# GNSS.net
KiCad netlist of a schematic drawn in Altium Designer
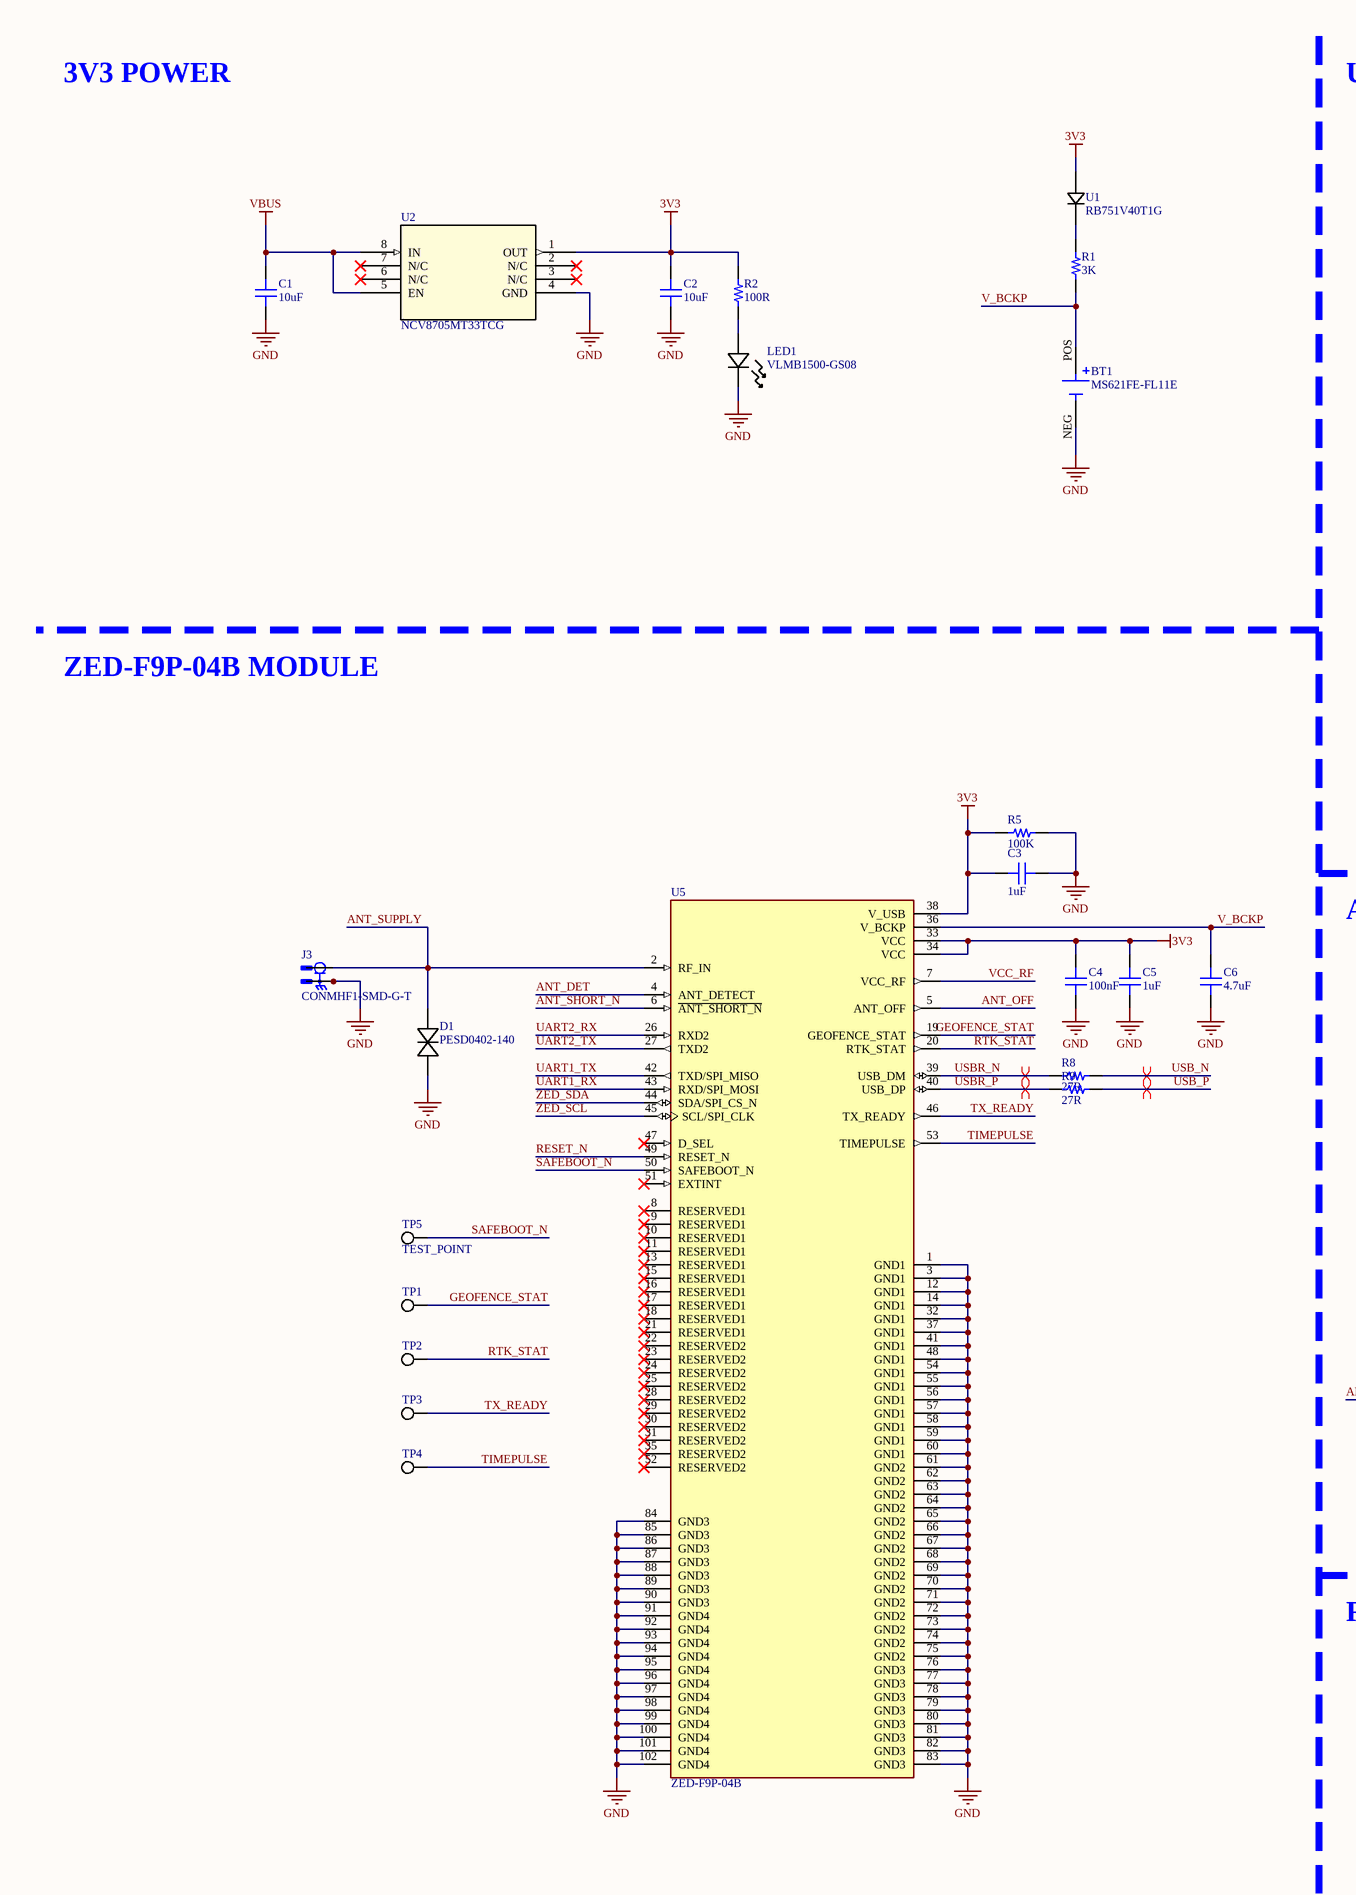
[diagram p0: GNSS.SchDoc, left]
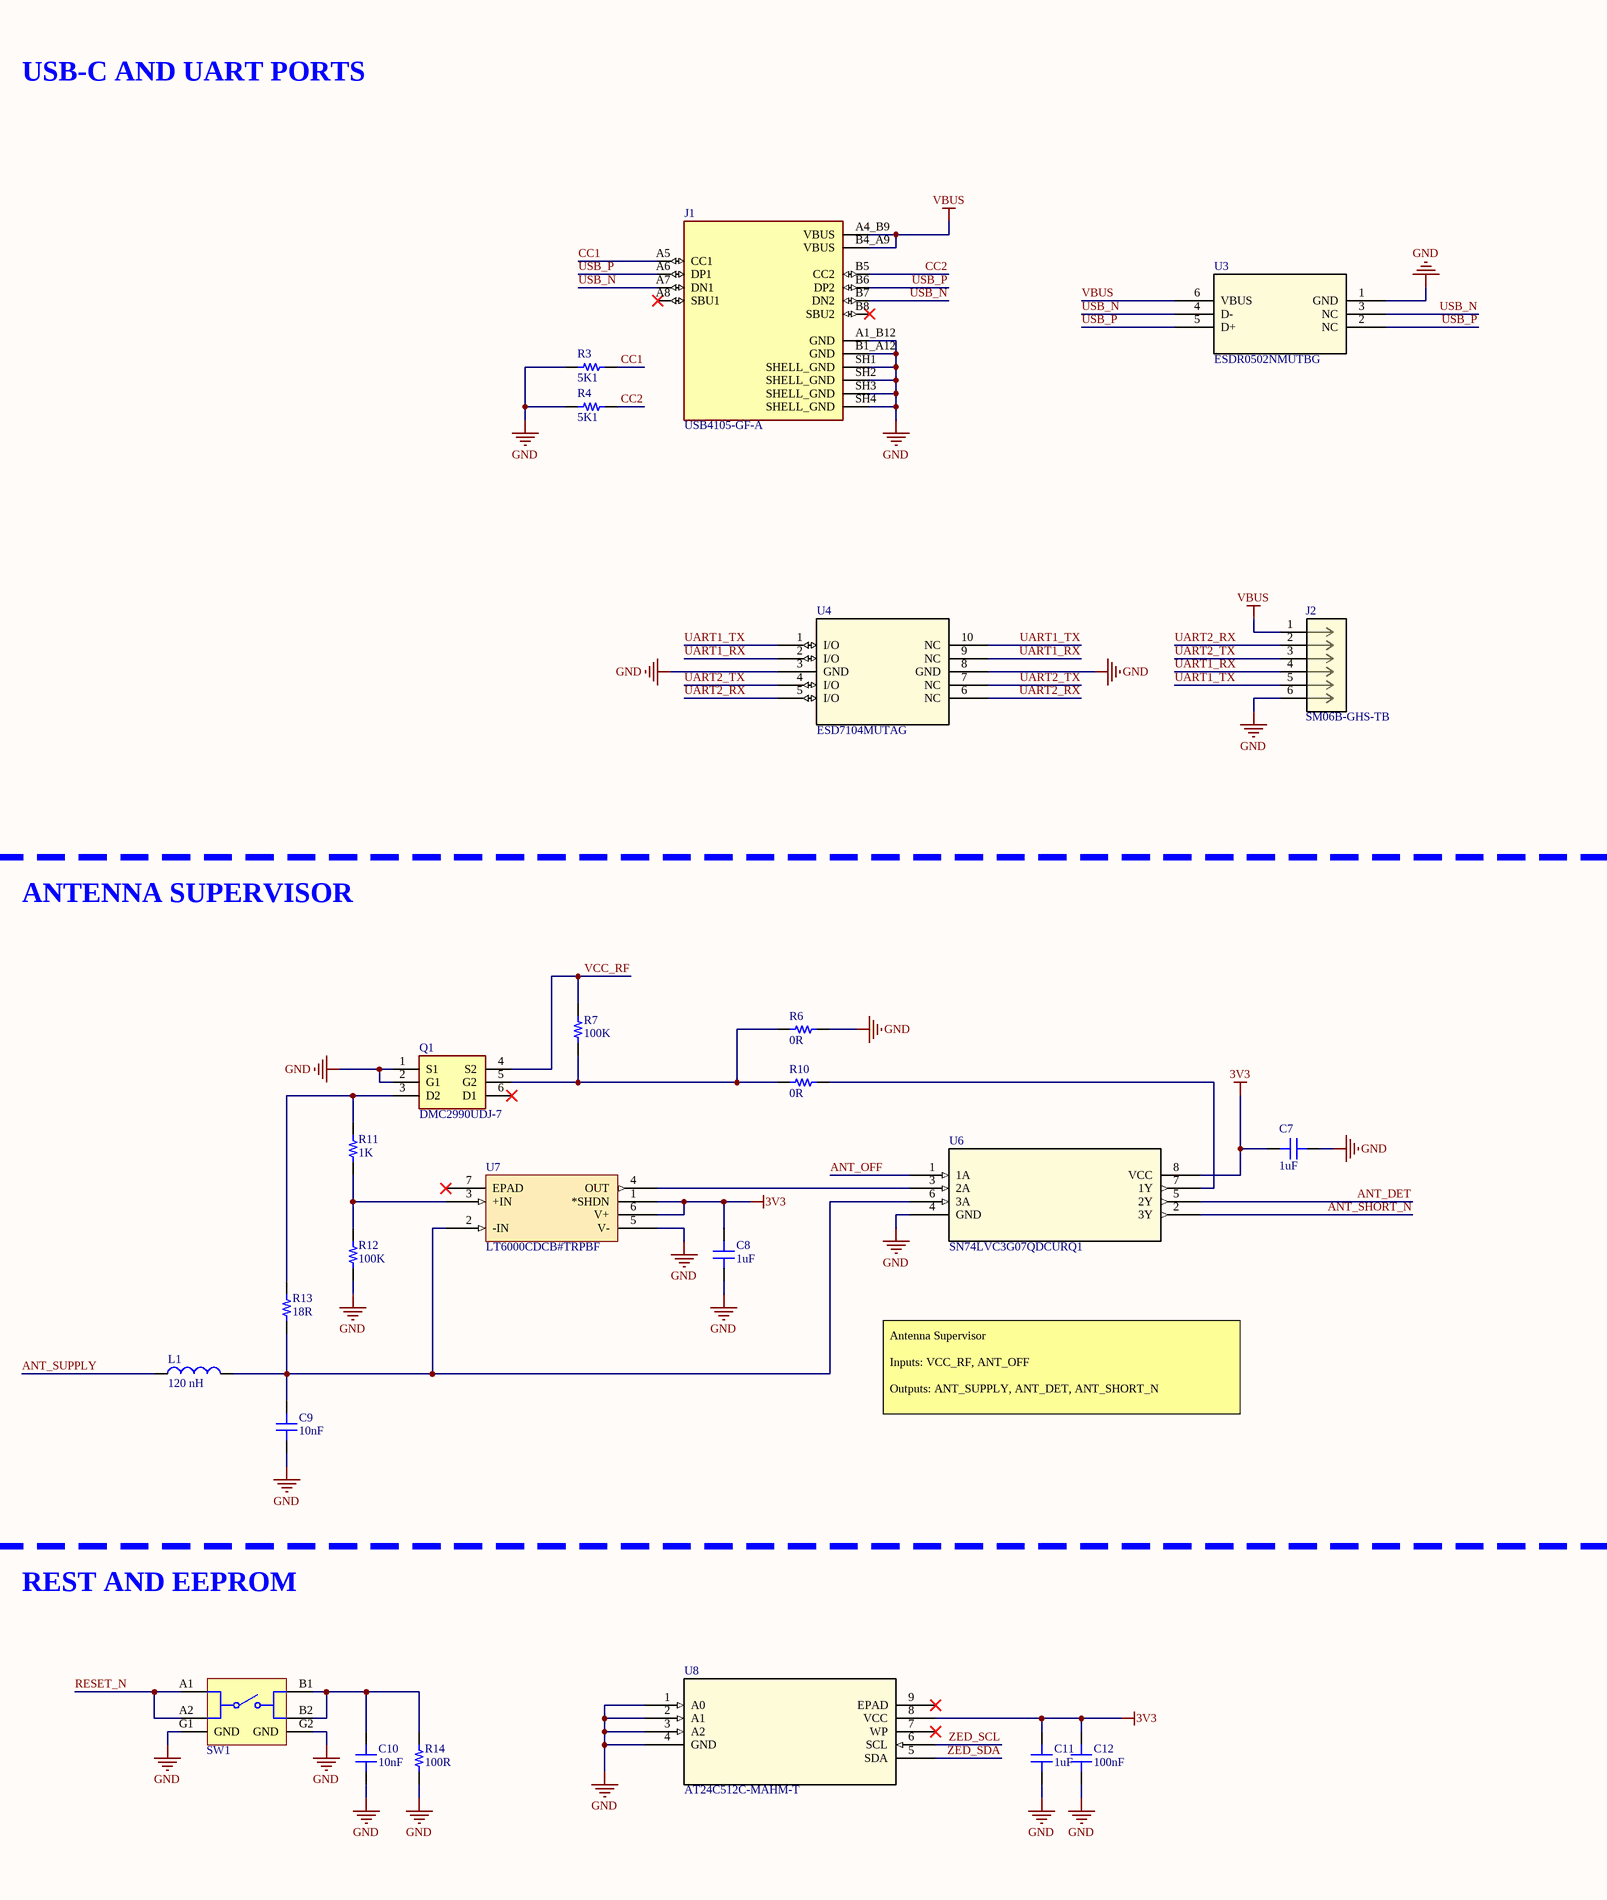
[diagram p1: GNSS.SchDoc, right]

(export (version "E")
  (design (tool "Eeschema 10.0.6"))
  (components
    (comp (ref "BT1")
      (value "MS621FE-FL11E")
      (footprint "BAT_MS621FE-FL11E")
      (description "Coin, 6.8mm 3 V Lithium Battery Rechargeable (Secondary) 5.5mAh")
      (fields (field (name "MF") "Seiko Instruments"))
      (libsource (lib "GPS-Module-Schlib") (part "MS621FE-FL11E"))
    )
    (comp (ref "C1")
      (value "10uF")
      (footprint "CAP 0402_1005")
      (description "Ceramic Capacitor, Ceramic, 10V, 20% +Tol, 20% -Tol, X5R, 15% TC, 10uF, Surface Mount, 0402")
      (fields (field (name "MANUFACTURER") "Murata") (field (name "MPN") "GRM155R61A106ME11D"))
      (libsource (lib "GPS-Module-Schlib") (part "GRM155R61A106ME11D"))
    )
    (comp (ref "C2")
      (value "10uF")
      (footprint "CAP 0402_1005")
      (description "Ceramic Capacitor, Ceramic, 10V, 20% +Tol, 20% -Tol, X5R, 15% TC, 10uF, Surface Mount, 0402")
      (fields (field (name "MANUFACTURER") "Murata") (field (name "MPN") "GRM155R61A106ME11D"))
      (libsource (lib "GPS-Module-Schlib") (part "GRM155R61A106ME11D"))
    )
    (comp (ref "C3")
      (value "1uF")
      (footprint "CAP 0402_1005")
      (description "Ceramic Capacitor, Ceramic, 16V, 10% +Tol, 10% -Tol, X6S, 22% TC, 1uF, Surface Mount, 0402")
      (fields (field (name "MANUFACTURER") "Murata") (field (name "MPN") "GRM155C81C105KE11D"))
      (libsource (lib "GPS-Module-Schlib") (part "GRM155C81C105KE11D"))
    )
    (comp (ref "C4")
      (value "100nF")
      (footprint "CAP 0402_1005")
      (description "Capacitor, Multilayer, Ceramic, 10V, 10%, X7R, 15% Tc, 0.1Uf, Surface Mount, 0402")
      (fields (field (name "MANUFACTURER") "KEMET") (field (name "MPN") "C0402C104K8RACTU"))
      (libsource (lib "GPS-Module-Schlib") (part "C0402C104K8RACTU"))
    )
    (comp (ref "C5")
      (value "1uF")
      (footprint "CAP 0402_1005")
      (description "Ceramic Capacitor, Ceramic, 16V, 10% +Tol, 10% -Tol, X6S, 22% TC, 1uF, Surface Mount, 0402")
      (fields (field (name "MANUFACTURER") "Murata") (field (name "MPN") "GRM155C81C105KE11D"))
      (libsource (lib "GPS-Module-Schlib") (part "GRM155C81C105KE11D"))
    )
    (comp (ref "C6")
      (value "4.7uF")
      (footprint "CAP 0603_1608")
      (description "Multilayer Ceramic Capacitor, CC Series, 4.7 - F, - 10%, X5R, 6.3 V, 0603 [1608 Metric]")
      (fields (field (name "MANUFACTURER") "Yageo Group") (field (name "MPN") "CC0603KRX5R5BB475"))
      (libsource (lib "GPS-Module-Schlib") (part "CC0603KRX5R5BB475"))
    )
    (comp (ref "C7")
      (value "1uF")
      (footprint "CAP 0402_1005")
      (description "Ceramic Capacitor, Ceramic, 16V, 10% +Tol, 10% -Tol, X6S, 22% TC, 1uF, Surface Mount, 0402")
      (fields (field (name "MANUFACTURER") "Murata") (field (name "MPN") "GRM155C81C105KE11D"))
      (libsource (lib "GPS-Module-Schlib") (part "GRM155C81C105KE11D"))
    )
    (comp (ref "C8")
      (value "1uF")
      (footprint "CAP 0402_1005")
      (description "Ceramic Capacitor, Ceramic, 16V, 10% +Tol, 10% -Tol, X6S, 22% TC, 1uF, Surface Mount, 0402")
      (fields (field (name "MANUFACTURER") "Murata") (field (name "MPN") "GRM155C81C105KE11D"))
      (libsource (lib "GPS-Module-Schlib") (part "GRM155C81C105KE11D"))
    )
    (comp (ref "C9")
      (value "10nF")
      (footprint "CAP 0402_1005")
      (description "0402 10000 pF 16 V ±10% Tolerance X7R Multilayer Ceramic Chip Capacitor")
      (fields (field (name "MANUFACTURER") "Murata") (field (name "MPN") "GRM155R71C103KA01D"))
      (libsource (lib "GPS-Module-Schlib") (part "GRM155R71C103KA01D"))
    )
    (comp (ref "C10")
      (value "10nF")
      (footprint "CAP 0402_1005")
      (description "Multilayer Ceramic Capacitors MLCC - SMD/SMT 25V 0.01uF X7R 0402 10%")
      (fields (field (name "MANUFACTURER") "KEMET") (field (name "MPN") "C0402C103K3REC7411"))
      (libsource (lib "GPS-Module-Schlib") (part "C0402C103K3REC7411"))
    )
    (comp (ref "C11")
      (value "1uF")
      (footprint "CAP 0402_1005")
      (description "Ceramic Capacitor, Ceramic, 16V, 10% +Tol, 10% -Tol, X6S, 22% TC, 1uF, Surface Mount, 0402")
      (fields (field (name "MANUFACTURER") "Murata") (field (name "MPN") "GRM155C81C105KE11D"))
      (libsource (lib "GPS-Module-Schlib") (part "GRM155C81C105KE11D"))
    )
    (comp (ref "C12")
      (value "100nF")
      (footprint "CAP 0402_1005")
      (description "Capacitor, Multilayer, Ceramic, 10V, 10%, X7R, 15% Tc, 0.1Uf, Surface Mount, 0402")
      (fields (field (name "MANUFACTURER") "KEMET") (field (name "MPN") "C0402C104K8RACTU"))
      (libsource (lib "GPS-Module-Schlib") (part "C0402C104K8RACTU"))
    )
    (comp (ref "D1")
      (value "PESD0402-140")
      (footprint "PESD0402-140_LTF")
      (description "TVS DIODE 14VWM 40VC 0402")
      (fields (field (name "COPYRIGHT") "Copyright (C) 2025 Ultra Librarian. All rights reserved."))
      (libsource (lib "GPS-Module-Schlib") (part "PESD0402-140"))
    )
    (comp (ref "J1")
      (value "USB4105-GF-A")
      (footprint "GCT_USB4105-GF-A")
      (description "CONN RCP USB2.0 TYP C 24P SMD RA")
      (fields (field (name "MF") "{'manufacturer': u'GCT'}"))
      (libsource (lib "GPS-Module-Schlib") (part "USB4105-GF-A"))
    )
    (comp (ref "J2")
      (value "SM06B-GHS-TB")
      (footprint "CONN_SM06B-GHS-TB_JST")
      (description "CONN HEADER SMD R/A 6POS 1.25MM")
      (fields (field (name "COPYRIGHT") "Copyright (C) 2025 Ultra Librarian. All rights reserved."))
      (libsource (lib "GPS-Module-Schlib") (part "SM06B-GHS-TB"))
    )
    (comp (ref "J3")
      (value "CONMHF1-SMD-G-T")
      (footprint "LINX_CONMHF1-SMD-G-T")
      (description "U.FL/MHF1 Jack 50 Ohm PCB Surface Mount")
      (fields (field (name "MF") "TE Connectivity"))
      (libsource (lib "GPS-Module-Schlib") (part "CONMHF1-SMD-G-T"))
    )
    (comp (ref "L1")
      (value "120 nH")
      (footprint "INDC1005X60N")
      (description "Inductor with Inductance: 120nH Tol. +/-5%, Package: 0402 _1005_")
      (fields (field (name "DIGI-KEY_PART_NUMBER") "490-4091-1-ND") (field (name "MPN") "LQW15ANR12J00D"))
      (libsource (lib "GPS-Module-Schlib") (part "LQW15ANR12J00D"))
    )
    (comp (ref "LED1")
      (value "VLMB1500-GS08")
      (footprint "LED_500-GS08_VIS")
      (description "CHIPLED(0402) BLUE ULTRABRIGHT -e4")
      (fields (field (name "COPYRIGHT") "Copyright (C) 2025 Ultra Librarian. All rights reserved."))
      (libsource (lib "GPS-Module-Schlib") (part "VLMB1500-GS08"))
    )
    (comp (ref "Q1")
      (value "DMC2990UDJ-7")
      (footprint "SOTFL35P100X50-6N")
      (description "Complem. Pair Enhancement MOSFET SOT-963")
      (fields (field (name "MOUSER PART NUMBER") "621-DMC2990UDJ-7"))
      (libsource (lib "GPS-Module-Schlib") (part "DMC2990UDJ-7"))
    )
    (comp (ref "R1")
      (value "3K")
      (footprint "RES 0402_1005")
      (description "Res Thick Film 0402 3K Ohm 1% 0.1W ±100ppm/°C Molded SMD Punched Carrier T/R")
      (fields (field (name "MANUFACTURER") "Panasonic") (field (name "MPN") "ERJ-2RKF3001X"))
      (libsource (lib "GPS-Module-Schlib") (part "ERJ-2RKF3001X"))
    )
    (comp (ref "R2")
      (value "100R")
      (footprint "RES 0402_1005")
      (description "Res Thick Film 0402 100 Ohm 1% 0.2W ±100ppm/°C Molded SMD SMD Paper T/R")
      (fields (field (name "MANUFACTURER") "Vishay") (field (name "MPN") "CRCW0402100RFKEDHP"))
      (libsource (lib "GPS-Module-Schlib") (part "CRCW0402100RFKEDHP"))
    )
    (comp (ref "R3")
      (value "5K1")
      (footprint "RES 0402_1005")
      (description "Res Thick Film 0402 5.1K Ohm 1% 0.063W(1/16W) ±100ppm/C Pad SMD T/R")
      (fields (field (name "MANUFACTURER") "Yageo Group") (field (name "MPN") "RC0402FR-135K1L"))
      (libsource (lib "GPS-Module-Schlib") (part "RC0402FR-135K1L"))
    )
    (comp (ref "R4")
      (value "5K1")
      (footprint "RES 0402_1005")
      (description "Res Thick Film 0402 5.1K Ohm 1% 0.063W(1/16W) ±100ppm/C Pad SMD T/R")
      (fields (field (name "MANUFACTURER") "Yageo Group") (field (name "MPN") "RC0402FR-135K1L"))
      (libsource (lib "GPS-Module-Schlib") (part "RC0402FR-135K1L"))
    )
    (comp (ref "R5")
      (value "100K")
      (footprint "RES 0402_1005")
      (description "Res Thick Film 0402 100K Ohm 1% 0.063W(1/16W) ±100ppm/C Pad SMD T/R")
      (fields (field (name "MANUFACTURER") "Vishay") (field (name "MPN") "CRCW0402100KFKEDC"))
      (libsource (lib "GPS-Module-Schlib") (part "CRCW0402100KFKEDC"))
    )
    (comp (ref "R6")
      (value "0R")
      (footprint "RES 0402_1005")
      (description "GENERAL PURPOSE CHIP RESISTOR Metal Glaze/thick Film, 0.0625W, 0ohm, Surface Mount, 0402")
      (fields (field (name "MANUFACTURER") "Yageo Group") (field (name "MPN") "RC0402JR-070RL"))
      (libsource (lib "GPS-Module-Schlib") (part "RC0402JR-070RL"))
    )
    (comp (ref "R7")
      (value "100K")
      (footprint "RES 0402_1005")
      (description "Res Thick Film 0402 100K Ohm 1% 0.063W(1/16W) ±100ppm/C Pad SMD T/R")
      (fields (field (name "MANUFACTURER") "Vishay") (field (name "MPN") "CRCW0402100KFKEDC"))
      (libsource (lib "GPS-Module-Schlib") (part "CRCW0402100KFKEDC"))
    )
    (comp (ref "R8")
      (value "27R")
      (footprint "RES 0402_1005")
      (description "Res General Purpose Thick Film 0402 27 Ohm 5% 1/16W ±100ppm/°C Molded SMD Paper T/R")
      (fields (field (name "MANUFACTURER") "Yageo Group") (field (name "MPN") "RC0402JR-0727RL"))
      (libsource (lib "GPS-Module-Schlib") (part "RC0402JR-0727RL"))
    )
    (comp (ref "R9")
      (value "27R")
      (footprint "RES 0402_1005")
      (description "Res General Purpose Thick Film 0402 27 Ohm 5% 1/16W ±100ppm/°C Molded SMD Paper T/R")
      (fields (field (name "MANUFACTURER") "Yageo Group") (field (name "MPN") "RC0402JR-0727RL"))
      (libsource (lib "GPS-Module-Schlib") (part "RC0402JR-0727RL"))
    )
    (comp (ref "R10")
      (value "0R")
      (footprint "RES 0402_1005")
      (description "GENERAL PURPOSE CHIP RESISTOR Metal Glaze/thick Film, 0.0625W, 0ohm, Surface Mount, 0402")
      (fields (field (name "MANUFACTURER") "Yageo Group") (field (name "MPN") "RC0402JR-070RL"))
      (libsource (lib "GPS-Module-Schlib") (part "RC0402JR-070RL"))
    )
    (comp (ref "R11")
      (value "1K")
      (footprint "RES 0402_1005")
      (description "Res Thick Film 0402 1K Ohm 1% 0.063W(1/16W) ±100ppm/C Pad SMD T/R")
      (fields (field (name "MANUFACTURER") "Vishay") (field (name "MPN") "CRCW04021K00FKEDC"))
      (libsource (lib "GPS-Module-Schlib") (part "CRCW04021K00FKEDC"))
    )
    (comp (ref "R12")
      (value "100K")
      (footprint "RES 0402_1005")
      (description "Res Thick Film 0402 100K Ohm 1% 0.063W(1/16W) ±100ppm/C Pad SMD T/R")
      (fields (field (name "MANUFACTURER") "Vishay") (field (name "MPN") "CRCW0402100KFKEDC"))
      (libsource (lib "GPS-Module-Schlib") (part "CRCW0402100KFKEDC"))
    )
    (comp (ref "R13")
      (value "18R")
      (footprint "RES 0402_1005")
      (description "Res Thick Film 0402 18 Ohm 1% 0.063W(1/16W) ±100ppm/C Pad SMD T/R")
      (fields (field (name "MANUFACTURER") "Bourns") (field (name "MPN") "CR0402-FX-18R0GLF"))
      (libsource (lib "GPS-Module-Schlib") (part "CR0402-FX-18R0GLF"))
    )
    (comp (ref "R14")
      (value "100R")
      (footprint "RES 0402_1005")
      (description "Res Thick Film 0402 100 Ohm 1% 0.2W ±100ppm/°C Molded SMD SMD Paper T/R")
      (fields (field (name "MANUFACTURER") "Vishay") (field (name "MPN") "CRCW0402100RFKEDHP"))
      (libsource (lib "GPS-Module-Schlib") (part "CRCW0402100RFKEDHP"))
    )
    (comp (ref "SW1")
      (value "435151014845")
      (footprint "435151014845")
      (description "WS-TASV SMT Tact Switch with ground terminal, L3 x W2.6 x H1.4mm, 450g, SPST-NO, 12V, 50mA")
      (fields (field (name "MANUFACTURER") "Wurth Elektronik"))
      (libsource (lib "GPS-Module-Schlib") (part "435151014845"))
    )
    (comp (ref "TP1")
      (value "TEST_POINT")
      (footprint "TEST_POINT")
      (libsource (lib "GPS-Module-Schlib") (part "TEST_POINT"))
    )
    (comp (ref "TP2")
      (value "TEST_POINT")
      (footprint "TEST_POINT")
      (libsource (lib "GPS-Module-Schlib") (part "TEST_POINT"))
    )
    (comp (ref "TP3")
      (value "TEST_POINT")
      (footprint "TEST_POINT")
      (libsource (lib "GPS-Module-Schlib") (part "TEST_POINT"))
    )
    (comp (ref "TP4")
      (value "TEST_POINT")
      (footprint "TEST_POINT")
      (libsource (lib "GPS-Module-Schlib") (part "TEST_POINT"))
    )
    (comp (ref "TP5")
      (value "TEST_POINT")
      (footprint "TEST_POINT")
      (libsource (lib "GPS-Module-Schlib") (part "TEST_POINT"))
    )
    (comp (ref "U1")
      (value "RB751V40T1G")
      (footprint "SOD-323_1P8X1P35_ONS")
      (description "Diode 30 V 30mA Surface Mount SOD-323")
      (fields (field (name "COPYRIGHT") "Copyright (C) 2025 Ultra Librarian. All rights reserved."))
      (libsource (lib "GPS-Module-Schlib") (part "RB751V40T1G"))
    )
    (comp (ref "U2")
      (value "NCV8705MT33TCG")
      (footprint "WDFN6_2X2_ONS")
      (description "Linear Voltage Regulator IC Positive Fixed 1 Output 500mA 6-WDFN (2x2)")
      (fields (field (name "COPYRIGHT") "Copyright (C) 2025 Ultra Librarian. All rights reserved."))
      (libsource (lib "GPS-Module-Schlib") (part "NCV8705MT33TCG"))
    )
    (comp (ref "U3")
      (value "ESDR0502NMUTBG")
      (footprint "UDFN6_517AA_ONS")
      (description "TVS DIODE 5.5VWM 6UDFN")
      (fields (field (name "COPYRIGHT") "Copyright (C) 2025 Ultra Librarian. All rights reserved."))
      (libsource (lib "GPS-Module-Schlib") (part "ESDR0502NMUTBG"))
    )
    (comp (ref "U4")
      (value "ESD7104MUTAG")
      (footprint "UDFN10_ONS_ESD")
      (description "TVS DIODE 5VWM 10VC 10UDFN")
      (fields (field (name "COPYRIGHT") "Copyright (C) 2025 Ultra Librarian. All rights reserved."))
      (libsource (lib "GPS-Module-Schlib") (part "ESD7104MUTAG"))
    )
    (comp (ref "U5")
      (value "ZED-F9P-04B")
      (footprint "MODULE_ZED-F9P-04B")
      (fields (field (name "MF") "U-Blox"))
      (libsource (lib "GPS-Module-Schlib") (part "ZED-F9P-04B"))
    )
    (comp (ref "U6")
      (value "SN74LVC3G07QDCURQ1")
      (footprint "DCU8_TEX_SN74")
      (description "Automotive 3-ch, 1.65-V to 5.5-V buffers with open-drain outputs 8-VSSOP -40 to 125")
      (fields (field (name "COPYRIGHT") "Copyright (C) 2025 Ultra Librarian. All rights reserved."))
      (libsource (lib "GPS-Module-Schlib") (part "SN74LVC3G07QDCURQ1"))
    )
    (comp (ref "U7")
      (value "LT6000CDCB#TRPBF")
      (footprint "DFN-6_DCB")
      (description "Op Amp Single Low Power Amplifier R-R I/O 18V Automotive 6-Pin DFN EP T/R")
      (fields (field (name "MF") "Analog Devices"))
      (libsource (lib "GPS-Module-Schlib") (part "LT6000CDCB#TRPBF"))
    )
    (comp (ref "U8")
      (value "AT24C512C-MAHM-T")
      (footprint "8MA2_ATM_EEPROM")
      (description "IC EEPROM 512KBIT I2C 8UDFN")
      (fields (field (name "COPYRIGHT") "Copyright (C) 2025 Ultra Librarian. All rights reserved."))
      (libsource (lib "GPS-Module-Schlib") (part "AT24C512C-MAHM-T"))
    )
  )
  (nets
    (net (code "1") (name "/ANT_DET") (class "Default")
      (node (ref "U5") (pin "4") (pinfunction "ANT_DETECT_4") (pintype "input"))
      (node (ref "U6") (pin "5") (pinfunction "2Y_5") (pintype "output"))
    )
    (net (code "2") (name "/ANT_OFF") (class "Default")
      (node (ref "U5") (pin "5") (pinfunction "ANT_OFF_5") (pintype "output"))
      (node (ref "U6") (pin "1") (pinfunction "1A_1") (pintype "input"))
    )
    (net (code "3") (name "/ANT_SHORT_N") (class "Default")
      (node (ref "U5") (pin "6") (pinfunction "~{ANT_SHORT_N}_6") (pintype "input"))
      (node (ref "U6") (pin "2") (pinfunction "3Y_2") (pintype "output"))
    )
    (net (code "4") (name "/ANT_SUPPLY") (class "Default")
      (node (ref "D1") (pin "1") (pinfunction "1_1") (pintype "passive"))
      (node (ref "J3") (pin "1") (pinfunction "1_1") (pintype "passive"))
      (node (ref "L1") (pin "1") (pinfunction "1_1") (pintype "passive"))
      (node (ref "U5") (pin "2") (pinfunction "RF_IN_2") (pintype "input"))
    )
    (net (code "5") (name "/CC1") (class "Default")
      (node (ref "J1") (pin "A5") (pinfunction "CC1_A5") (pintype "bidirectional"))
      (node (ref "R3") (pin "1") (pinfunction "1_1") (pintype "passive"))
    )
    (net (code "6") (name "/CC2") (class "Default")
      (node (ref "J1") (pin "B5") (pinfunction "CC2_B5") (pintype "bidirectional"))
      (node (ref "R4") (pin "2") (pinfunction "2_2") (pintype "passive"))
    )
    (net (code "7") (name "/GEOFENCE_STAT") (class "Default")
      (node (ref "TP1") (pin "1") (pinfunction "1_1") (pintype "passive"))
      (node (ref "U5") (pin "19") (pinfunction "GEOFENCE_STAT_19") (pintype "output"))
    )
    (net (code "8") (name "/RESET_N") (class "Default")
      (node (ref "SW1") (pin "A1") (pinfunction "A1_A1") (pintype "passive"))
      (node (ref "SW1") (pin "A2") (pinfunction "A2_A2") (pintype "passive"))
      (node (ref "U5") (pin "49") (pinfunction "RESET_N_49") (pintype "input"))
    )
    (net (code "9") (name "/RTK_STAT") (class "Default")
      (node (ref "TP2") (pin "1") (pinfunction "1_1") (pintype "passive"))
      (node (ref "U5") (pin "20") (pinfunction "RTK_STAT_20") (pintype "output"))
    )
    (net (code "10") (name "/SAFEBOOT_N") (class "Default")
      (node (ref "TP5") (pin "1") (pinfunction "1_1") (pintype "passive"))
      (node (ref "U5") (pin "50") (pinfunction "SAFEBOOT_N_50") (pintype "input"))
    )
    (net (code "11") (name "/TIMEPULSE") (class "Default")
      (node (ref "TP4") (pin "1") (pinfunction "1_1") (pintype "passive"))
      (node (ref "U5") (pin "53") (pinfunction "TIMEPULSE_53") (pintype "output"))
    )
    (net (code "12") (name "/TX_READY") (class "Default")
      (node (ref "TP3") (pin "1") (pinfunction "1_1") (pintype "passive"))
      (node (ref "U5") (pin "46") (pinfunction "TX_READY_46") (pintype "output"))
    )
    (net (code "13") (name "/UART1_RX") (class "Default")
      (node (ref "J2") (pin "4") (pinfunction "4_4") (pintype "passive"))
      (node (ref "U4") (pin "2") (pinfunction "I/O_2") (pintype "bidirectional"))
      (node (ref "U4") (pin "9") (pinfunction "NC_9") (pintype "passive"))
      (node (ref "U5") (pin "43") (pinfunction "RXD/SPI_MOSI_43") (pintype "input"))
    )
    (net (code "14") (name "/UART1_TX") (class "Default")
      (node (ref "J2") (pin "5") (pinfunction "5_5") (pintype "passive"))
      (node (ref "U4") (pin "1") (pinfunction "I/O_1") (pintype "bidirectional"))
      (node (ref "U4") (pin "10") (pinfunction "NC_10") (pintype "passive"))
      (node (ref "U5") (pin "42") (pinfunction "TXD/SPI_MISO_42") (pintype "output"))
    )
    (net (code "15") (name "/UART2_RX") (class "Default")
      (node (ref "J2") (pin "2") (pinfunction "2_2") (pintype "passive"))
      (node (ref "U4") (pin "5") (pinfunction "I/O_5") (pintype "bidirectional"))
      (node (ref "U4") (pin "6") (pinfunction "NC_6") (pintype "passive"))
      (node (ref "U5") (pin "26") (pinfunction "RXD2_26") (pintype "input"))
    )
    (net (code "16") (name "/UART2_TX") (class "Default")
      (node (ref "J2") (pin "3") (pinfunction "3_3") (pintype "passive"))
      (node (ref "U4") (pin "4") (pinfunction "I/O_4") (pintype "bidirectional"))
      (node (ref "U4") (pin "7") (pinfunction "NC_7") (pintype "passive"))
      (node (ref "U5") (pin "27") (pinfunction "TXD2_27") (pintype "output"))
    )
    (net (code "17") (name "/USBR_N") (class "Default")
      (node (ref "R8") (pin "1") (pinfunction "1_1") (pintype "passive"))
      (node (ref "U5") (pin "39") (pinfunction "USB_DM_39") (pintype "bidirectional"))
    )
    (net (code "18") (name "/USBR_P") (class "Default")
      (node (ref "R9") (pin "1") (pinfunction "1_1") (pintype "passive"))
      (node (ref "U5") (pin "40") (pinfunction "USB_DP_40") (pintype "bidirectional"))
    )
    (net (code "19") (name "/USB_N") (class "Default")
      (node (ref "J1") (pin "A7") (pinfunction "DN1_A7") (pintype "bidirectional"))
      (node (ref "J1") (pin "B7") (pinfunction "DN2_B7") (pintype "bidirectional"))
      (node (ref "R8") (pin "2") (pinfunction "2_2") (pintype "passive"))
      (node (ref "U3") (pin "3") (pinfunction "NC_3") (pintype "passive"))
      (node (ref "U3") (pin "4") (pinfunction "D-_4") (pintype "passive"))
    )
    (net (code "20") (name "/USB_P") (class "Default")
      (node (ref "J1") (pin "A6") (pinfunction "DP1_A6") (pintype "bidirectional"))
      (node (ref "J1") (pin "B6") (pinfunction "DP2_B6") (pintype "bidirectional"))
      (node (ref "R9") (pin "2") (pinfunction "2_2") (pintype "passive"))
      (node (ref "U3") (pin "2") (pinfunction "NC_2") (pintype "passive"))
      (node (ref "U3") (pin "5") (pinfunction "D+_5") (pintype "passive"))
    )
    (net (code "21") (name "/VCC_RF") (class "Default")
      (node (ref "Q1") (pin "4") (pinfunction "S2_4") (pintype "passive"))
      (node (ref "R7") (pin "2") (pinfunction "2_2") (pintype "passive"))
      (node (ref "U5") (pin "7") (pinfunction "VCC_RF_7") (pintype "output"))
    )
    (net (code "22") (name "/V_BCKP") (class "Default")
      (node (ref "BT1") (pin "POS") (pinfunction "POS_POS") (pintype "passive"))
      (node (ref "C6") (pin "1") (pinfunction "1_1") (pintype "passive"))
      (node (ref "R1") (pin "1") (pinfunction "1_1") (pintype "passive"))
      (node (ref "U5") (pin "36") (pinfunction "V_BCKP_36") (pintype "power_in"))
    )
    (net (code "23") (name "/ZED_SCL") (class "Default")
      (node (ref "U5") (pin "45") (pinfunction "SCL/SPI_CLK_45") (pintype "bidirectional"))
      (node (ref "U8") (pin "6") (pinfunction "SCL_6") (pintype "input"))
    )
    (net (code "24") (name "/ZED_SDA") (class "Default")
      (node (ref "U5") (pin "44") (pinfunction "SDA/SPI_CS_N_44") (pintype "bidirectional"))
      (node (ref "U8") (pin "5") (pinfunction "SDA_5") (pintype "passive"))
    )
    (net (code "25") (name "3V3") (class "Default")
      (node (ref "C11") (pin "1") (pinfunction "1_1") (pintype "passive"))
      (node (ref "C12") (pin "1") (pinfunction "1_1") (pintype "passive"))
      (node (ref "C2") (pin "2") (pinfunction "2_2") (pintype "passive"))
      (node (ref "C3") (pin "2") (pinfunction "2_2") (pintype "passive"))
      (node (ref "C4") (pin "2") (pinfunction "2_2") (pintype "passive"))
      (node (ref "C5") (pin "2") (pinfunction "2_2") (pintype "passive"))
      (node (ref "C7") (pin "2") (pinfunction "2_2") (pintype "passive"))
      (node (ref "C8") (pin "2") (pinfunction "2_2") (pintype "passive"))
      (node (ref "R2") (pin "2") (pinfunction "2_2") (pintype "passive"))
      (node (ref "R5") (pin "2") (pinfunction "2_2") (pintype "passive"))
      (node (ref "U1") (pin "2") (pinfunction "2_2") (pintype "passive"))
      (node (ref "U2") (pin "1") (pinfunction "OUT_1") (pintype "output"))
      (node (ref "U5") (pin "33") (pinfunction "VCC_33") (pintype "power_in"))
      (node (ref "U5") (pin "34") (pinfunction "VCC_34") (pintype "power_in"))
      (node (ref "U5") (pin "38") (pinfunction "V_USB_38") (pintype "power_in"))
      (node (ref "U6") (pin "8") (pinfunction "VCC_8") (pintype "power_in"))
      (node (ref "U7") (pin "1") (pinfunction "*SHDN_1") (pintype "passive"))
      (node (ref "U7") (pin "6") (pinfunction "V+_6") (pintype "power_in"))
      (node (ref "U8") (pin "8") (pinfunction "VCC_8") (pintype "power_in"))
    )
    (net (code "26") (name "GND") (class "Default")
      (node (ref "BT1") (pin "NEG") (pinfunction "NEG_NEG") (pintype "passive"))
      (node (ref "C1") (pin "1") (pinfunction "1_1") (pintype "passive"))
      (node (ref "C10") (pin "1") (pinfunction "1_1") (pintype "passive"))
      (node (ref "C11") (pin "2") (pinfunction "2_2") (pintype "passive"))
      (node (ref "C12") (pin "2") (pinfunction "2_2") (pintype "passive"))
      (node (ref "C2") (pin "1") (pinfunction "1_1") (pintype "passive"))
      (node (ref "C3") (pin "1") (pinfunction "1_1") (pintype "passive"))
      (node (ref "C4") (pin "1") (pinfunction "1_1") (pintype "passive"))
      (node (ref "C5") (pin "1") (pinfunction "1_1") (pintype "passive"))
      (node (ref "C6") (pin "2") (pinfunction "2_2") (pintype "passive"))
      (node (ref "C7") (pin "1") (pinfunction "1_1") (pintype "passive"))
      (node (ref "C8") (pin "1") (pinfunction "1_1") (pintype "passive"))
      (node (ref "C9") (pin "1") (pinfunction "1_1") (pintype "passive"))
      (node (ref "D1") (pin "2") (pinfunction "2_2") (pintype "passive"))
      (node (ref "J1") (pin "A1_B12") (pinfunction "GND_A1_B12") (pintype "power_in"))
      (node (ref "J1") (pin "B1_A12") (pinfunction "GND_B1_A12") (pintype "power_in"))
      (node (ref "J1") (pin "SH1") (pinfunction "SHELL_GND_SH1") (pintype "power_in"))
      (node (ref "J1") (pin "SH2") (pinfunction "SHELL_GND_SH2") (pintype "power_in"))
      (node (ref "J1") (pin "SH3") (pinfunction "SHELL_GND_SH3") (pintype "power_in"))
      (node (ref "J1") (pin "SH4") (pinfunction "SHELL_GND_SH4") (pintype "power_in"))
      (node (ref "J2") (pin "6") (pinfunction "6_6") (pintype "passive"))
      (node (ref "J3") (pin "S1") (pinfunction "2_S1") (pintype "passive"))
      (node (ref "J3") (pin "S2") (pinfunction "2_S2") (pintype "passive"))
      (node (ref "J3") (pin "S3") (pinfunction "2_S3") (pintype "passive"))
      (node (ref "LED1") (pin "1") (pinfunction "1_1") (pintype "passive"))
      (node (ref "Q1") (pin "1") (pinfunction "S1_1") (pintype "passive"))
      (node (ref "Q1") (pin "2") (pinfunction "G1_2") (pintype "passive"))
      (node (ref "R12") (pin "1") (pinfunction "1_1") (pintype "passive"))
      (node (ref "R14") (pin "1") (pinfunction "1_1") (pintype "passive"))
      (node (ref "R3") (pin "2") (pinfunction "2_2") (pintype "passive"))
      (node (ref "R4") (pin "1") (pinfunction "1_1") (pintype "passive"))
      (node (ref "R5") (pin "1") (pinfunction "1_1") (pintype "passive"))
      (node (ref "R6") (pin "2") (pinfunction "2_2") (pintype "passive"))
      (node (ref "SW1") (pin "G1") (pinfunction "GND_G1") (pintype "passive"))
      (node (ref "SW1") (pin "G2") (pinfunction "GND_G2") (pintype "passive"))
      (node (ref "U2") (pin "4") (pinfunction "GND_4") (pintype "power_in"))
      (node (ref "U3") (pin "1") (pinfunction "GND_1") (pintype "power_in"))
      (node (ref "U4") (pin "3") (pinfunction "GND_3") (pintype "power_in"))
      (node (ref "U4") (pin "8") (pinfunction "GND_8") (pintype "power_in"))
      (node (ref "U5") (pin "1") (pinfunction "GND1_1") (pintype "power_in"))
      (node (ref "U5") (pin "100") (pinfunction "GND4_100") (pintype "power_in"))
      (node (ref "U5") (pin "101") (pinfunction "GND4_101") (pintype "power_in"))
      (node (ref "U5") (pin "102") (pinfunction "GND4_102") (pintype "power_in"))
      (node (ref "U5") (pin "12") (pinfunction "GND1_12") (pintype "power_in"))
      (node (ref "U5") (pin "14") (pinfunction "GND1_14") (pintype "power_in"))
      (node (ref "U5") (pin "3") (pinfunction "GND1_3") (pintype "power_in"))
      (node (ref "U5") (pin "32") (pinfunction "GND1_32") (pintype "power_in"))
      (node (ref "U5") (pin "37") (pinfunction "GND1_37") (pintype "power_in"))
      (node (ref "U5") (pin "41") (pinfunction "GND1_41") (pintype "power_in"))
      (node (ref "U5") (pin "48") (pinfunction "GND1_48") (pintype "power_in"))
      (node (ref "U5") (pin "54") (pinfunction "GND1_54") (pintype "power_in"))
      (node (ref "U5") (pin "55") (pinfunction "GND1_55") (pintype "power_in"))
      (node (ref "U5") (pin "56") (pinfunction "GND1_56") (pintype "power_in"))
      (node (ref "U5") (pin "57") (pinfunction "GND1_57") (pintype "power_in"))
      (node (ref "U5") (pin "58") (pinfunction "GND1_58") (pintype "power_in"))
      (node (ref "U5") (pin "59") (pinfunction "GND1_59") (pintype "power_in"))
      (node (ref "U5") (pin "60") (pinfunction "GND1_60") (pintype "power_in"))
      (node (ref "U5") (pin "61") (pinfunction "GND2_61") (pintype "power_in"))
      (node (ref "U5") (pin "62") (pinfunction "GND2_62") (pintype "power_in"))
      (node (ref "U5") (pin "63") (pinfunction "GND2_63") (pintype "power_in"))
      (node (ref "U5") (pin "64") (pinfunction "GND2_64") (pintype "power_in"))
      (node (ref "U5") (pin "65") (pinfunction "GND2_65") (pintype "power_in"))
      (node (ref "U5") (pin "66") (pinfunction "GND2_66") (pintype "power_in"))
      (node (ref "U5") (pin "67") (pinfunction "GND2_67") (pintype "power_in"))
      (node (ref "U5") (pin "68") (pinfunction "GND2_68") (pintype "power_in"))
      (node (ref "U5") (pin "69") (pinfunction "GND2_69") (pintype "power_in"))
      (node (ref "U5") (pin "70") (pinfunction "GND2_70") (pintype "power_in"))
      (node (ref "U5") (pin "71") (pinfunction "GND2_71") (pintype "power_in"))
      (node (ref "U5") (pin "72") (pinfunction "GND2_72") (pintype "power_in"))
      (node (ref "U5") (pin "73") (pinfunction "GND2_73") (pintype "power_in"))
      (node (ref "U5") (pin "74") (pinfunction "GND2_74") (pintype "power_in"))
      (node (ref "U5") (pin "75") (pinfunction "GND2_75") (pintype "power_in"))
      (node (ref "U5") (pin "76") (pinfunction "GND3_76") (pintype "power_in"))
      (node (ref "U5") (pin "77") (pinfunction "GND3_77") (pintype "power_in"))
      (node (ref "U5") (pin "78") (pinfunction "GND3_78") (pintype "power_in"))
      (node (ref "U5") (pin "79") (pinfunction "GND3_79") (pintype "power_in"))
      (node (ref "U5") (pin "80") (pinfunction "GND3_80") (pintype "power_in"))
      (node (ref "U5") (pin "81") (pinfunction "GND3_81") (pintype "power_in"))
      (node (ref "U5") (pin "82") (pinfunction "GND3_82") (pintype "power_in"))
      (node (ref "U5") (pin "83") (pinfunction "GND3_83") (pintype "power_in"))
      (node (ref "U5") (pin "84") (pinfunction "GND3_84") (pintype "power_in"))
      (node (ref "U5") (pin "85") (pinfunction "GND3_85") (pintype "power_in"))
      (node (ref "U5") (pin "86") (pinfunction "GND3_86") (pintype "power_in"))
      (node (ref "U5") (pin "87") (pinfunction "GND3_87") (pintype "power_in"))
      (node (ref "U5") (pin "88") (pinfunction "GND3_88") (pintype "power_in"))
      (node (ref "U5") (pin "89") (pinfunction "GND3_89") (pintype "power_in"))
      (node (ref "U5") (pin "90") (pinfunction "GND3_90") (pintype "power_in"))
      (node (ref "U5") (pin "91") (pinfunction "GND4_91") (pintype "power_in"))
      (node (ref "U5") (pin "92") (pinfunction "GND4_92") (pintype "power_in"))
      (node (ref "U5") (pin "93") (pinfunction "GND4_93") (pintype "power_in"))
      (node (ref "U5") (pin "94") (pinfunction "GND4_94") (pintype "power_in"))
      (node (ref "U5") (pin "95") (pinfunction "GND4_95") (pintype "power_in"))
      (node (ref "U5") (pin "96") (pinfunction "GND4_96") (pintype "power_in"))
      (node (ref "U5") (pin "97") (pinfunction "GND4_97") (pintype "power_in"))
      (node (ref "U5") (pin "98") (pinfunction "GND4_98") (pintype "power_in"))
      (node (ref "U5") (pin "99") (pinfunction "GND4_99") (pintype "power_in"))
      (node (ref "U6") (pin "4") (pinfunction "GND_4") (pintype "power_in"))
      (node (ref "U7") (pin "5") (pinfunction "V-_5") (pintype "power_in"))
      (node (ref "U8") (pin "1") (pinfunction "A0_1") (pintype "input"))
      (node (ref "U8") (pin "2") (pinfunction "A1_2") (pintype "input"))
      (node (ref "U8") (pin "3") (pinfunction "A2_3") (pintype "input"))
      (node (ref "U8") (pin "4") (pinfunction "GND_4") (pintype "power_in"))
    )
    (net (code "27") (name "Net-(C10-Pad2)") (class "Default")
      (node (ref "C10") (pin "2") (pinfunction "2_2") (pintype "passive"))
      (node (ref "R14") (pin "2") (pinfunction "2_2") (pintype "passive"))
      (node (ref "SW1") (pin "B1") (pinfunction "B1_B1") (pintype "passive"))
      (node (ref "SW1") (pin "B2") (pinfunction "B2_B2") (pintype "passive"))
    )
    (net (code "28") (name "Net-(LED1-Pad2)") (class "Default")
      (node (ref "LED1") (pin "2") (pinfunction "2_2") (pintype "passive"))
      (node (ref "R2") (pin "1") (pinfunction "1_1") (pintype "passive"))
    )
    (net (code "29") (name "Net-(Q1-D2)") (class "Default")
      (node (ref "Q1") (pin "3") (pinfunction "D2_3") (pintype "passive"))
      (node (ref "R11") (pin "2") (pinfunction "2_2") (pintype "passive"))
      (node (ref "R13") (pin "2") (pinfunction "2_2") (pintype "passive"))
    )
    (net (code "30") (name "Net-(Q1-G2)") (class "Default")
      (node (ref "Q1") (pin "5") (pinfunction "G2_5") (pintype "passive"))
      (node (ref "R10") (pin "1") (pinfunction "1_1") (pintype "passive"))
      (node (ref "R6") (pin "1") (pinfunction "1_1") (pintype "passive"))
      (node (ref "R7") (pin "1") (pinfunction "1_1") (pintype "passive"))
    )
    (net (code "31") (name "Net-(R1-Pad2)") (class "Default")
      (node (ref "R1") (pin "2") (pinfunction "2_2") (pintype "passive"))
      (node (ref "U1") (pin "1") (pinfunction "1_1") (pintype "passive"))
    )
    (net (code "32") (name "Net-(U6-1Y)") (class "Default")
      (node (ref "R10") (pin "2") (pinfunction "2_2") (pintype "passive"))
      (node (ref "U6") (pin "7") (pinfunction "1Y_7") (pintype "output"))
    )
    (net (code "33") (name "Net-(U6-2A)") (class "Default")
      (node (ref "U6") (pin "3") (pinfunction "2A_3") (pintype "input"))
      (node (ref "U7") (pin "4") (pinfunction "OUT_4") (pintype "output"))
    )
    (net (code "34") (name "Net-(U6-3A)") (class "Default")
      (node (ref "C9") (pin "2") (pinfunction "2_2") (pintype "passive"))
      (node (ref "L1") (pin "2") (pinfunction "2_2") (pintype "passive"))
      (node (ref "R13") (pin "1") (pinfunction "1_1") (pintype "passive"))
      (node (ref "U6") (pin "6") (pinfunction "3A_6") (pintype "input"))
      (node (ref "U7") (pin "2") (pinfunction "-IN_2") (pintype "input"))
    )
    (net (code "35") (name "Net-(U7-+IN)") (class "Default")
      (node (ref "R11") (pin "1") (pinfunction "1_1") (pintype "passive"))
      (node (ref "R12") (pin "2") (pinfunction "2_2") (pintype "passive"))
      (node (ref "U7") (pin "3") (pinfunction "+IN_3") (pintype "input"))
    )
    (net (code "36") (name "VBUS") (class "Default")
      (node (ref "C1") (pin "2") (pinfunction "2_2") (pintype "passive"))
      (node (ref "J1") (pin "A4_B9") (pinfunction "VBUS_A4_B9") (pintype "power_in"))
      (node (ref "J1") (pin "B4_A9") (pinfunction "VBUS_B4_A9") (pintype "power_in"))
      (node (ref "J2") (pin "1") (pinfunction "1_1") (pintype "passive"))
      (node (ref "U2") (pin "5") (pinfunction "EN_5") (pintype "passive"))
      (node (ref "U2") (pin "8") (pinfunction "IN_8") (pintype "input"))
      (node (ref "U3") (pin "6") (pinfunction "VBUS_6") (pintype "power_in"))
    )
    (net (code "37") (name "unconnected-(J1-SBU1-PadA8)") (class "Default")
      (node (ref "J1") (pin "A8") (pinfunction "SBU1_A8") (pintype "bidirectional+no_connect"))
    )
    (net (code "38") (name "unconnected-(J1-SBU2-PadB8)") (class "Default")
      (node (ref "J1") (pin "B8") (pinfunction "SBU2_B8") (pintype "bidirectional+no_connect"))
    )
    (net (code "39") (name "unconnected-(Q1-D1-Pad6)") (class "Default")
      (node (ref "Q1") (pin "6") (pinfunction "D1_6") (pintype "passive+no_connect"))
    )
    (net (code "40") (name "unconnected-(U2-N{slash}C-Pad2)") (class "Default")
      (node (ref "U2") (pin "2") (pinfunction "N/C_2") (pintype "passive+no_connect"))
    )
    (net (code "41") (name "unconnected-(U2-N{slash}C-Pad3)") (class "Default")
      (node (ref "U2") (pin "3") (pinfunction "N/C_3") (pintype "passive+no_connect"))
    )
    (net (code "42") (name "unconnected-(U2-N{slash}C-Pad6)") (class "Default")
      (node (ref "U2") (pin "6") (pinfunction "N/C_6") (pintype "passive+no_connect"))
    )
    (net (code "43") (name "unconnected-(U2-N{slash}C-Pad7)") (class "Default")
      (node (ref "U2") (pin "7") (pinfunction "N/C_7") (pintype "passive+no_connect"))
    )
    (net (code "44") (name "unconnected-(U5-D_SEL-Pad47)") (class "Default")
      (node (ref "U5") (pin "47") (pinfunction "D_SEL_47") (pintype "input+no_connect"))
    )
    (net (code "45") (name "unconnected-(U5-EXTINT-Pad51)") (class "Default")
      (node (ref "U5") (pin "51") (pinfunction "EXTINT_51") (pintype "input+no_connect"))
    )
    (net (code "46") (name "unconnected-(U5-RESERVED1-Pad8)") (class "Default")
      (node (ref "U5") (pin "8") (pinfunction "RESERVED1_8") (pintype "passive+no_connect"))
    )
    (net (code "47") (name "unconnected-(U5-RESERVED1-Pad9)") (class "Default")
      (node (ref "U5") (pin "9") (pinfunction "RESERVED1_9") (pintype "passive+no_connect"))
    )
    (net (code "48") (name "unconnected-(U5-RESERVED1-Pad10)") (class "Default")
      (node (ref "U5") (pin "10") (pinfunction "RESERVED1_10") (pintype "passive+no_connect"))
    )
    (net (code "49") (name "unconnected-(U5-RESERVED1-Pad11)") (class "Default")
      (node (ref "U5") (pin "11") (pinfunction "RESERVED1_11") (pintype "passive+no_connect"))
    )
    (net (code "50") (name "unconnected-(U5-RESERVED1-Pad13)") (class "Default")
      (node (ref "U5") (pin "13") (pinfunction "RESERVED1_13") (pintype "passive+no_connect"))
    )
    (net (code "51") (name "unconnected-(U5-RESERVED1-Pad15)") (class "Default")
      (node (ref "U5") (pin "15") (pinfunction "RESERVED1_15") (pintype "passive+no_connect"))
    )
    (net (code "52") (name "unconnected-(U5-RESERVED1-Pad16)") (class "Default")
      (node (ref "U5") (pin "16") (pinfunction "RESERVED1_16") (pintype "passive+no_connect"))
    )
    (net (code "53") (name "unconnected-(U5-RESERVED1-Pad17)") (class "Default")
      (node (ref "U5") (pin "17") (pinfunction "RESERVED1_17") (pintype "passive+no_connect"))
    )
    (net (code "54") (name "unconnected-(U5-RESERVED1-Pad18)") (class "Default")
      (node (ref "U5") (pin "18") (pinfunction "RESERVED1_18") (pintype "passive+no_connect"))
    )
    (net (code "55") (name "unconnected-(U5-RESERVED1-Pad21)") (class "Default")
      (node (ref "U5") (pin "21") (pinfunction "RESERVED1_21") (pintype "passive+no_connect"))
    )
    (net (code "56") (name "unconnected-(U5-RESERVED2-Pad22)") (class "Default")
      (node (ref "U5") (pin "22") (pinfunction "RESERVED2_22") (pintype "passive+no_connect"))
    )
    (net (code "57") (name "unconnected-(U5-RESERVED2-Pad23)") (class "Default")
      (node (ref "U5") (pin "23") (pinfunction "RESERVED2_23") (pintype "passive+no_connect"))
    )
    (net (code "58") (name "unconnected-(U5-RESERVED2-Pad24)") (class "Default")
      (node (ref "U5") (pin "24") (pinfunction "RESERVED2_24") (pintype "passive+no_connect"))
    )
    (net (code "59") (name "unconnected-(U5-RESERVED2-Pad25)") (class "Default")
      (node (ref "U5") (pin "25") (pinfunction "RESERVED2_25") (pintype "passive+no_connect"))
    )
    (net (code "60") (name "unconnected-(U5-RESERVED2-Pad28)") (class "Default")
      (node (ref "U5") (pin "28") (pinfunction "RESERVED2_28") (pintype "passive+no_connect"))
    )
    (net (code "61") (name "unconnected-(U5-RESERVED2-Pad29)") (class "Default")
      (node (ref "U5") (pin "29") (pinfunction "RESERVED2_29") (pintype "passive+no_connect"))
    )
    (net (code "62") (name "unconnected-(U5-RESERVED2-Pad30)") (class "Default")
      (node (ref "U5") (pin "30") (pinfunction "RESERVED2_30") (pintype "passive+no_connect"))
    )
    (net (code "63") (name "unconnected-(U5-RESERVED2-Pad31)") (class "Default")
      (node (ref "U5") (pin "31") (pinfunction "RESERVED2_31") (pintype "passive+no_connect"))
    )
    (net (code "64") (name "unconnected-(U5-RESERVED2-Pad35)") (class "Default")
      (node (ref "U5") (pin "35") (pinfunction "RESERVED2_35") (pintype "passive+no_connect"))
    )
    (net (code "65") (name "unconnected-(U5-RESERVED2-Pad52)") (class "Default")
      (node (ref "U5") (pin "52") (pinfunction "RESERVED2_52") (pintype "passive+no_connect"))
    )
    (net (code "66") (name "unconnected-(U7-EPAD-Pad7)") (class "Default")
      (node (ref "U7") (pin "7") (pinfunction "EPAD_7") (pintype "passive+no_connect"))
    )
    (net (code "67") (name "unconnected-(U8-EPAD-Pad9)") (class "Default")
      (node (ref "U8") (pin "9") (pinfunction "EPAD_9") (pintype "passive+no_connect"))
    )
    (net (code "68") (name "unconnected-(U8-WP-Pad7)") (class "Default")
      (node (ref "U8") (pin "7") (pinfunction "WP_7") (pintype "passive+no_connect"))
    )
  )
)
